# charlieplex20_minres.net
KiCad netlist of a schematic drawn in EAGLE
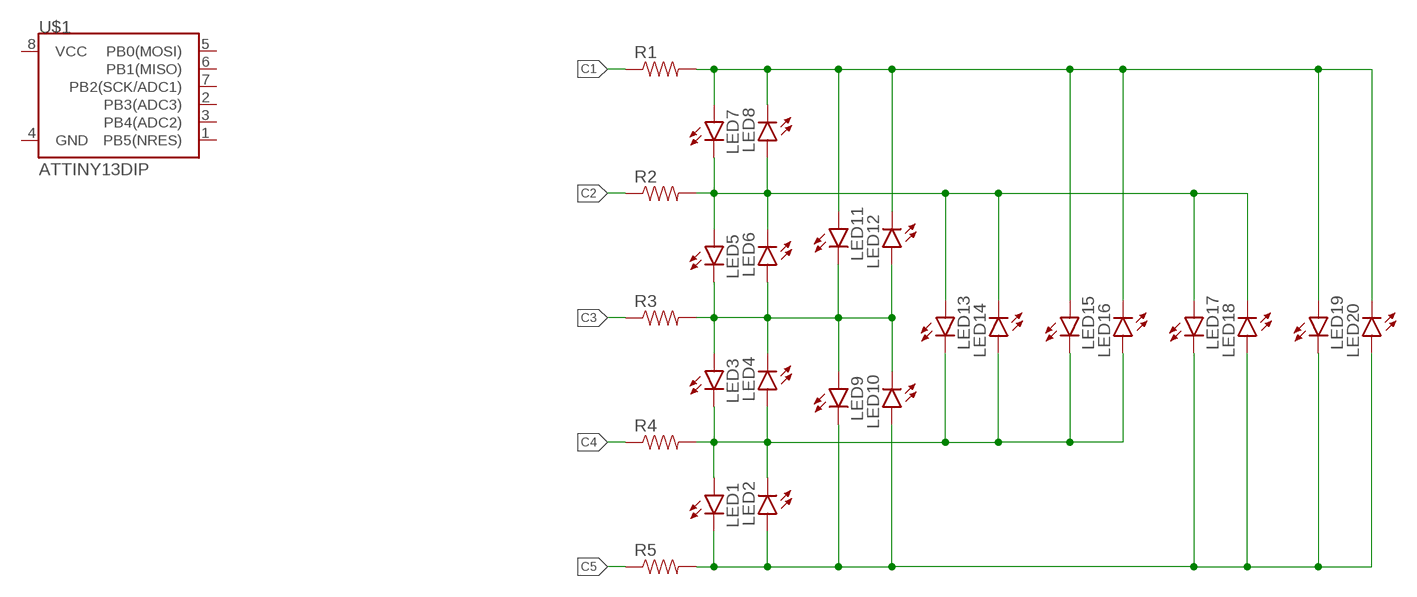
[diagram p0: schematic, sheet 1]

(export (version "E")
  (design (tool "Eeschema 10.0.6"))
  (components
    (comp (ref "LED1")
      (value "LED0603")
      (footprint "eagle-import:LED-0603")
      (libsource (lib "eagle-import") (part "LED0603"))
    )
    (comp (ref "LED2")
      (value "LED0603")
      (footprint "eagle-import:LED-0603")
      (libsource (lib "eagle-import") (part "LED0603"))
    )
    (comp (ref "LED3")
      (value "LED0603")
      (footprint "eagle-import:LED-0603")
      (libsource (lib "eagle-import") (part "LED0603"))
    )
    (comp (ref "LED4")
      (value "LED0603")
      (footprint "eagle-import:LED-0603")
      (libsource (lib "eagle-import") (part "LED0603"))
    )
    (comp (ref "LED5")
      (value "LED0603")
      (footprint "eagle-import:LED-0603")
      (libsource (lib "eagle-import") (part "LED0603"))
    )
    (comp (ref "LED6")
      (value "LED0603")
      (footprint "eagle-import:LED-0603")
      (libsource (lib "eagle-import") (part "LED0603"))
    )
    (comp (ref "LED7")
      (value "LED0603")
      (footprint "eagle-import:LED-0603")
      (libsource (lib "eagle-import") (part "LED0603"))
    )
    (comp (ref "LED8")
      (value "LED0603")
      (footprint "eagle-import:LED-0603")
      (libsource (lib "eagle-import") (part "LED0603"))
    )
    (comp (ref "LED9")
      (value "LED0603")
      (footprint "eagle-import:LED-0603")
      (libsource (lib "eagle-import") (part "LED0603"))
    )
    (comp (ref "LED10")
      (value "LED0603")
      (footprint "eagle-import:LED-0603")
      (libsource (lib "eagle-import") (part "LED0603"))
    )
    (comp (ref "LED11")
      (value "LED0603")
      (footprint "eagle-import:LED-0603")
      (libsource (lib "eagle-import") (part "LED0603"))
    )
    (comp (ref "LED12")
      (value "LED0603")
      (footprint "eagle-import:LED-0603")
      (libsource (lib "eagle-import") (part "LED0603"))
    )
    (comp (ref "LED13")
      (value "LED0603")
      (footprint "eagle-import:LED-0603")
      (libsource (lib "eagle-import") (part "LED0603"))
    )
    (comp (ref "LED14")
      (value "LED0603")
      (footprint "eagle-import:LED-0603")
      (libsource (lib "eagle-import") (part "LED0603"))
    )
    (comp (ref "LED15")
      (value "LED0603")
      (footprint "eagle-import:LED-0603")
      (libsource (lib "eagle-import") (part "LED0603"))
    )
    (comp (ref "LED16")
      (value "LED0603")
      (footprint "eagle-import:LED-0603")
      (libsource (lib "eagle-import") (part "LED0603"))
    )
    (comp (ref "LED17")
      (value "LED0603")
      (footprint "eagle-import:LED-0603")
      (libsource (lib "eagle-import") (part "LED0603"))
    )
    (comp (ref "LED18")
      (value "LED0603")
      (footprint "eagle-import:LED-0603")
      (libsource (lib "eagle-import") (part "LED0603"))
    )
    (comp (ref "LED19")
      (value "LED0603")
      (footprint "eagle-import:LED-0603")
      (libsource (lib "eagle-import") (part "LED0603"))
    )
    (comp (ref "LED20")
      (value "LED0603")
      (footprint "eagle-import:LED-0603")
      (libsource (lib "eagle-import") (part "LED0603"))
    )
    (comp (ref "R1")
      (value "RESISTOR0603-RES")
      (footprint "eagle-import:0603-RES")
      (libsource (lib "eagle-import") (part "RESISTOR0603-RES"))
    )
    (comp (ref "R2")
      (value "RESISTOR0603-RES")
      (footprint "eagle-import:0603-RES")
      (libsource (lib "eagle-import") (part "RESISTOR0603-RES"))
    )
    (comp (ref "R3")
      (value "RESISTOR0603-RES")
      (footprint "eagle-import:0603-RES")
      (libsource (lib "eagle-import") (part "RESISTOR0603-RES"))
    )
    (comp (ref "R4")
      (value "RESISTOR0603-RES")
      (footprint "eagle-import:0603-RES")
      (libsource (lib "eagle-import") (part "RESISTOR0603-RES"))
    )
    (comp (ref "R5")
      (value "RESISTOR0603-RES")
      (footprint "eagle-import:0603-RES")
      (libsource (lib "eagle-import") (part "RESISTOR0603-RES"))
    )
    (comp (ref "U$1")
      (value "ATTINY13DIP")
      (footprint "eagle-import:DIP08")
      (libsource (lib "eagle-import") (part "ATTINY13DIP"))
    )
  )
  (nets
    (net (code "1") (name "C1") (class "Default")
      (node (ref "LED11") (pin "A") (pinfunction "A_A") (pintype "passive"))
      (node (ref "LED12") (pin "C") (pinfunction "C_C") (pintype "passive"))
      (node (ref "LED15") (pin "A") (pinfunction "A_A") (pintype "passive"))
      (node (ref "LED16") (pin "C") (pinfunction "C_C") (pintype "passive"))
      (node (ref "LED19") (pin "A") (pinfunction "A_A") (pintype "passive"))
      (node (ref "LED20") (pin "C") (pinfunction "C_C") (pintype "passive"))
      (node (ref "LED7") (pin "A") (pinfunction "A_A") (pintype "passive"))
      (node (ref "LED8") (pin "C") (pinfunction "C_C") (pintype "passive"))
      (node (ref "R1") (pin "1") (pinfunction "1_1") (pintype "passive"))
      (node (ref "R1") (pin "2") (pinfunction "2_2") (pintype "passive"))
    )
    (net (code "2") (name "C2") (class "Default")
      (node (ref "LED13") (pin "A") (pinfunction "A_A") (pintype "passive"))
      (node (ref "LED14") (pin "C") (pinfunction "C_C") (pintype "passive"))
      (node (ref "LED17") (pin "A") (pinfunction "A_A") (pintype "passive"))
      (node (ref "LED18") (pin "C") (pinfunction "C_C") (pintype "passive"))
      (node (ref "LED5") (pin "A") (pinfunction "A_A") (pintype "passive"))
      (node (ref "LED6") (pin "C") (pinfunction "C_C") (pintype "passive"))
      (node (ref "LED7") (pin "C") (pinfunction "C_C") (pintype "passive"))
      (node (ref "LED8") (pin "A") (pinfunction "A_A") (pintype "passive"))
      (node (ref "R2") (pin "1") (pinfunction "1_1") (pintype "passive"))
      (node (ref "R2") (pin "2") (pinfunction "2_2") (pintype "passive"))
    )
    (net (code "3") (name "C3") (class "Default")
      (node (ref "LED10") (pin "C") (pinfunction "C_C") (pintype "passive"))
      (node (ref "LED11") (pin "C") (pinfunction "C_C") (pintype "passive"))
      (node (ref "LED12") (pin "A") (pinfunction "A_A") (pintype "passive"))
      (node (ref "LED3") (pin "A") (pinfunction "A_A") (pintype "passive"))
      (node (ref "LED4") (pin "C") (pinfunction "C_C") (pintype "passive"))
      (node (ref "LED5") (pin "C") (pinfunction "C_C") (pintype "passive"))
      (node (ref "LED6") (pin "A") (pinfunction "A_A") (pintype "passive"))
      (node (ref "LED9") (pin "A") (pinfunction "A_A") (pintype "passive"))
      (node (ref "R3") (pin "1") (pinfunction "1_1") (pintype "passive"))
      (node (ref "R3") (pin "2") (pinfunction "2_2") (pintype "passive"))
    )
    (net (code "4") (name "C4") (class "Default")
      (node (ref "LED1") (pin "A") (pinfunction "A_A") (pintype "passive"))
      (node (ref "LED13") (pin "C") (pinfunction "C_C") (pintype "passive"))
      (node (ref "LED14") (pin "A") (pinfunction "A_A") (pintype "passive"))
      (node (ref "LED15") (pin "C") (pinfunction "C_C") (pintype "passive"))
      (node (ref "LED16") (pin "A") (pinfunction "A_A") (pintype "passive"))
      (node (ref "LED2") (pin "C") (pinfunction "C_C") (pintype "passive"))
      (node (ref "LED3") (pin "C") (pinfunction "C_C") (pintype "passive"))
      (node (ref "LED4") (pin "A") (pinfunction "A_A") (pintype "passive"))
      (node (ref "R4") (pin "1") (pinfunction "1_1") (pintype "passive"))
      (node (ref "R4") (pin "2") (pinfunction "2_2") (pintype "passive"))
    )
    (net (code "5") (name "C5") (class "Default")
      (node (ref "LED1") (pin "C") (pinfunction "C_C") (pintype "passive"))
      (node (ref "LED10") (pin "A") (pinfunction "A_A") (pintype "passive"))
      (node (ref "LED17") (pin "C") (pinfunction "C_C") (pintype "passive"))
      (node (ref "LED18") (pin "A") (pinfunction "A_A") (pintype "passive"))
      (node (ref "LED19") (pin "C") (pinfunction "C_C") (pintype "passive"))
      (node (ref "LED2") (pin "A") (pinfunction "A_A") (pintype "passive"))
      (node (ref "LED20") (pin "A") (pinfunction "A_A") (pintype "passive"))
      (node (ref "LED9") (pin "C") (pinfunction "C_C") (pintype "passive"))
      (node (ref "R5") (pin "1") (pinfunction "1_1") (pintype "passive"))
      (node (ref "R5") (pin "2") (pinfunction "2_2") (pintype "passive"))
    )
    (net (code "6") (name "unconnected-(U$1-GND-Pad4)") (class "Default")
      (node (ref "U$1") (pin "4") (pinfunction "GND_4") (pintype "bidirectional"))
    )
    (net (code "7") (name "unconnected-(U$1-PB0(MOSI)-Pad5)") (class "Default")
      (node (ref "U$1") (pin "5") (pinfunction "PB0(MOSI)_5") (pintype "bidirectional"))
    )
    (net (code "8") (name "unconnected-(U$1-PB1(MISO)-Pad6)") (class "Default")
      (node (ref "U$1") (pin "6") (pinfunction "PB1(MISO)_6") (pintype "bidirectional"))
    )
    (net (code "9") (name "unconnected-(U$1-PB2(SCK{slash}ADC1)-Pad7)") (class "Default")
      (node (ref "U$1") (pin "7") (pinfunction "PB2(SCK/ADC1)_7") (pintype "bidirectional"))
    )
    (net (code "10") (name "unconnected-(U$1-PB3(ADC3)-Pad2)") (class "Default")
      (node (ref "U$1") (pin "2") (pinfunction "PB3(ADC3)_2") (pintype "bidirectional"))
    )
    (net (code "11") (name "unconnected-(U$1-PB4(ADC2)-Pad3)") (class "Default")
      (node (ref "U$1") (pin "3") (pinfunction "PB4(ADC2)_3") (pintype "bidirectional"))
    )
    (net (code "12") (name "unconnected-(U$1-PB5(NRES)-Pad1)") (class "Default")
      (node (ref "U$1") (pin "1") (pinfunction "PB5(NRES)_1") (pintype "bidirectional"))
    )
    (net (code "13") (name "unconnected-(U$1-VCC-Pad8)") (class "Default")
      (node (ref "U$1") (pin "8") (pinfunction "VCC_8") (pintype "bidirectional"))
    )
  )
)
